# K60.net
KiCad netlist of a schematic drawn in Altium Designer
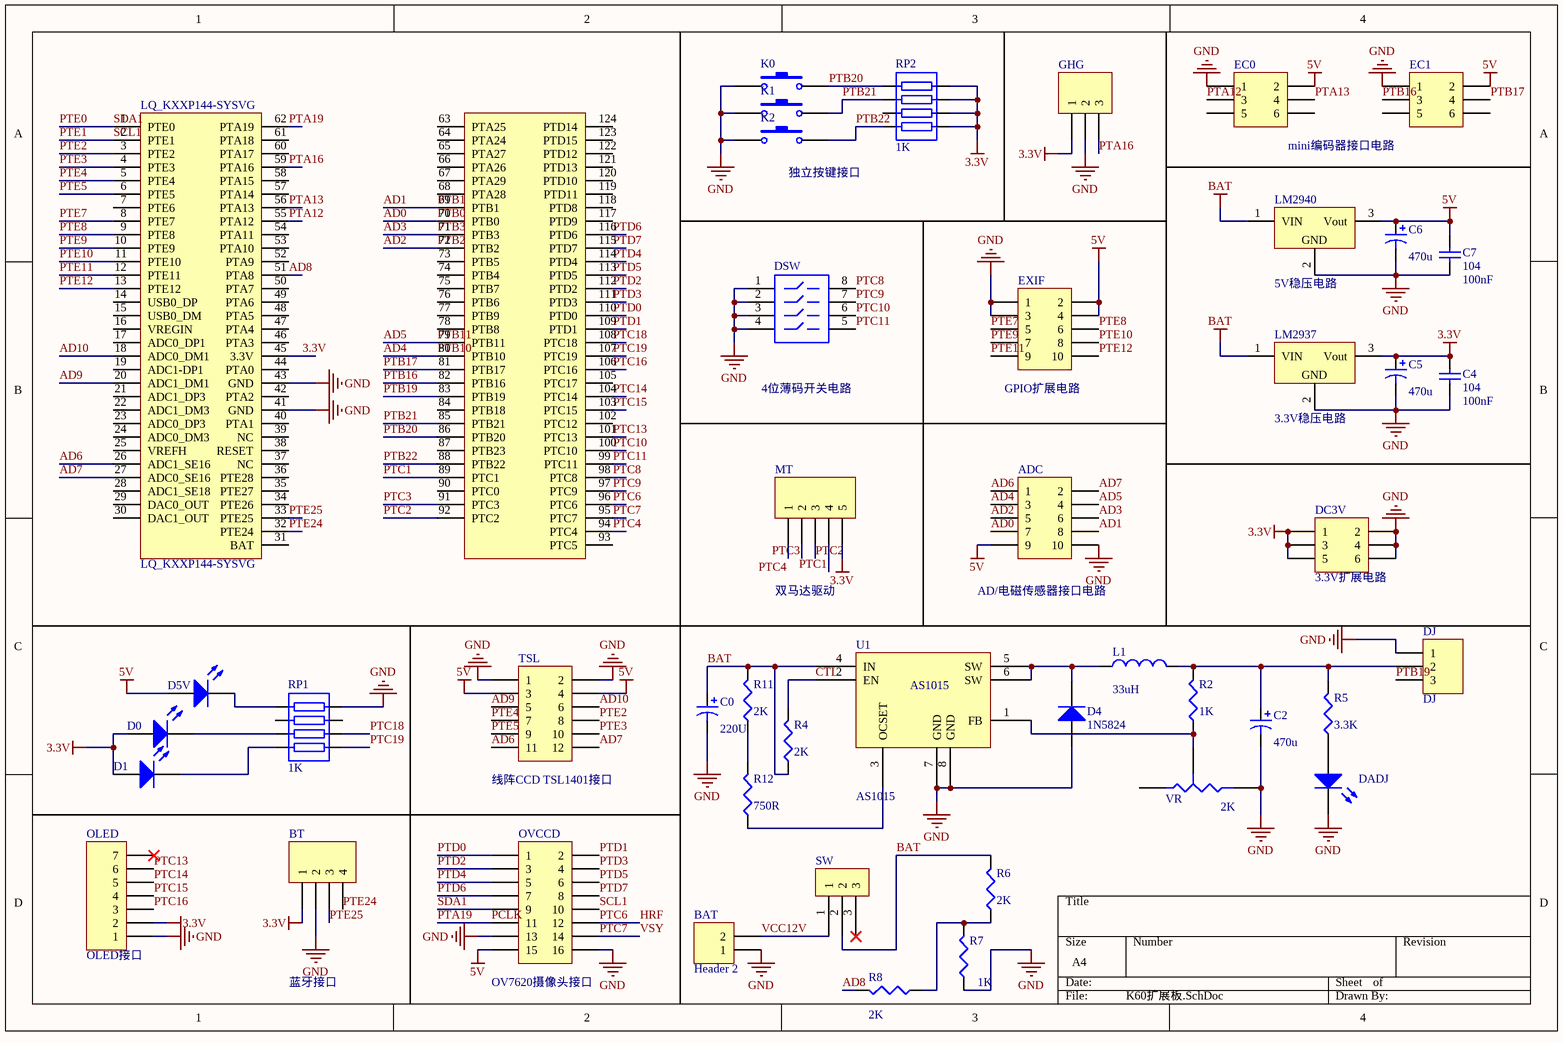
[diagram p0: K60扩展板.SchDoc]

(export (version "E")
  (design (tool "Eeschema 10.0.6"))
  (components
    (comp (ref "ADC")
      (value "AD/电磁传感器接口电路")
      (footprint "HDR2X5")
      (description "Header, 5-Pin, Dual row")
      (fields (field (name "PUBLISHER") "Altium Limited"))
      (libsource (lib "Miscellaneous Connectors") (part "Header 5X2"))
    )
    (comp (ref "BAT")
      (value "Header 2")
      (footprint "power1")
      (description "Header, 2-Pin")
      (fields (field (name "PUBLISHER") "Altium Limited"))
      (libsource (lib "Miscellaneous Connectors") (part "Header 2"))
    )
    (comp (ref "BT")
      (value "蓝牙接口")
      (footprint "HDR1X4")
      (description "Header, 4-Pin")
      (fields (field (name "PUBLISHER") "Altium Limited"))
      (libsource (lib "Miscellaneous Connectors") (part "Header 4"))
    )
    (comp (ref "C0")
      (value "220U")
      (footprint "rb -5")
      (description "Polarized Capacitor (Radial)")
      (fields (field (name "PUBLISHER") "Altium Limited"))
      (libsource (lib "Miscellaneous Devices") (part "Cap Pol1"))
    )
    (comp (ref "C2")
      (value "470u")
      (footprint "3527")
      (description "Polarized Capacitor (Surface Mount)")
      (fields (field (name "PUBLISHER") "Altium Limited"))
      (libsource (lib "Miscellaneous Devices") (part "Cap Pol3"))
    )
    (comp (ref "C4")
      (value "104")
      (footprint "Miscellaneous Devices:0603")
      (description "Capacitor (Semiconductor SIM Model)")
      (fields (field (name "ALTIUM_VALUE") "100nF") (field (name "PUBLISHER") "Altium Limited"))
      (libsource (lib "Miscellaneous Devices") (part "Cap Semi"))
    )
    (comp (ref "C5")
      (value "470u")
      (footprint "3527")
      (description "Polarized Capacitor (Surface Mount)")
      (fields (field (name "PUBLISHER") "Altium Limited"))
      (libsource (lib "Miscellaneous Devices") (part "Cap Pol3"))
    )
    (comp (ref "C6")
      (value "470u")
      (footprint "3527")
      (description "Polarized Capacitor (Surface Mount)")
      (fields (field (name "PUBLISHER") "Altium Limited"))
      (libsource (lib "Miscellaneous Devices") (part "Cap Pol3"))
    )
    (comp (ref "C7")
      (value "104")
      (footprint "Miscellaneous Devices:0603")
      (description "Capacitor (Semiconductor SIM Model)")
      (fields (field (name "ALTIUM_VALUE") "100nF") (field (name "PUBLISHER") "Altium Limited"))
      (libsource (lib "Miscellaneous Devices") (part "Cap Semi"))
    )
    (comp (ref "D0")
      (value "~")
      (footprint "3.2X1.6X1.1")
      (description "Typical BLUE SiC LED")
      (fields (field (name "PUBLISHER") "Altium Limited"))
      (libsource (lib "Miscellaneous Devices") (part "LED3"))
    )
    (comp (ref "D1")
      (value "~")
      (footprint "3.2X1.6X1.1")
      (description "Typical BLUE SiC LED")
      (fields (field (name "PUBLISHER") "Altium Limited"))
      (libsource (lib "Miscellaneous Devices") (part "LED3"))
    )
    (comp (ref "D4")
      (value "1N5824")
      (footprint "1812_DIODE")
      (description "Default Diode")
      (fields (field (name "PUBLISHER") "Altium Limited"))
      (libsource (lib "Miscellaneous Devices") (part "Diode"))
    )
    (comp (ref "D5V")
      (value "~")
      (footprint "3.2X1.6X1.1")
      (description "Typical BLUE SiC LED")
      (fields (field (name "PUBLISHER") "Altium Limited"))
      (libsource (lib "Miscellaneous Devices") (part "LED3"))
    )
    (comp (ref "DADJ")
      (value "~")
      (footprint "3.2X1.6X1.1")
      (description "Typical BLUE SiC LED")
      (fields (field (name "PUBLISHER") "Altium Limited"))
      (libsource (lib "Miscellaneous Devices") (part "LED3"))
    )
    (comp (ref "DC3V")
      (value "3.3V扩展电路")
      (footprint "HDR2X3")
      (description "Header, 3-Pin, Dual row, Right Angle")
      (fields (field (name "PUBLISHER") "Altium Limited"))
      (libsource (lib "Miscellaneous Connectors") (part "Header 3X2H"))
    )
    (comp (ref "DJ")
      (value "DJ")
      (footprint "HDR1X3")
      (description "Header, 3-Pin")
      (fields (field (name "PUBLISHER") "Altium Limited"))
      (libsource (lib "Miscellaneous Connectors") (part "Header 3"))
    )
    (comp (ref "DSW")
      (value "4位薄码开关电路")
      (footprint "DIP-8")
      (description "DIP Switch")
      (fields (field (name "PUBLISHER") "Altium Limited"))
      (libsource (lib "Miscellaneous Devices") (part "SW-DIP4"))
    )
    (comp (ref "EC0")
      (value "~")
      (footprint "HDR2X3")
      (description "Header, 3-Pin, Dual row")
      (fields (field (name "PUBLISHER") "Altium Limited"))
      (libsource (lib "Miscellaneous Connectors") (part "Header 3X2"))
    )
    (comp (ref "EC1")
      (value "mini编码器接口电路")
      (footprint "HDR2X3")
      (description "Header, 3-Pin, Dual row")
      (fields (field (name "PUBLISHER") "Altium Limited"))
      (libsource (lib "Miscellaneous Connectors") (part "Header 3X2"))
    )
    (comp (ref "EXIF")
      (value "GPIO扩展电路")
      (footprint "HDR2X5")
      (description "Header, 5-Pin, Dual row")
      (fields (field (name "PUBLISHER") "Altium Limited"))
      (libsource (lib "Miscellaneous Connectors") (part "Header 5X2"))
    )
    (comp (ref "GHG")
      (value "~")
      (footprint "HDR1X3")
      (description "Header, 3-Pin")
      (fields (field (name "PUBLISHER") "Altium Limited"))
      (libsource (lib "") (part "Header 3_1"))
    )
    (comp (ref "K0")
      (value "~")
      (footprint "2512R")
      (description "Switch")
      (fields (field (name "PUBLISHER") "Altium Limited"))
      (libsource (lib "Miscellaneous Devices") (part "SW-PB"))
    )
    (comp (ref "K1")
      (value "~")
      (footprint "2512R")
      (description "Switch")
      (fields (field (name "PUBLISHER") "Altium Limited"))
      (libsource (lib "Miscellaneous Devices") (part "SW-PB"))
    )
    (comp (ref "K2")
      (value "~")
      (footprint "2512R")
      (description "Switch")
      (fields (field (name "PUBLISHER") "Altium Limited"))
      (libsource (lib "Miscellaneous Devices") (part "SW-PB"))
    )
    (comp (ref "L1")
      (value "33uH")
      (footprint "CL1010")
      (description "Inductor")
      (fields (field (name "PUBLISHER") "Altium Limited"))
      (libsource (lib "Miscellaneous Devices") (part "Inductor"))
    )
    (comp (ref "LM2937")
      (value "3.3V稳压电路")
      (footprint "TO263-3")
      (description "固定5V输出直流稳压芯片")
      (libsource (lib "常用贴片器件库") (part "LM2940"))
    )
    (comp (ref "LM2940")
      (value "5V稳压电路")
      (footprint "TO263-3")
      (description "固定5V输出直流稳压芯片")
      (libsource (lib "常用贴片器件库") (part "LM2940"))
    )
    (comp (ref "LQ_KXXP144-SYSVG")
      (value "LQ_KXXP144-SYSVG")
      (footprint "LQ_KXXP144-SYSVG")
      (libsource (lib "LQ_KXXP144-SYSVGSCH") (part "LQ_KXXP144-SYSVG"))
    )
    (comp (ref "MT")
      (value "双马达驱动")
      (footprint "HDR1X5")
      (description "Header, 5-Pin")
      (fields (field (name "PUBLISHER") "Altium Limited"))
      (libsource (lib "Miscellaneous Connectors") (part "Header 5"))
    )
    (comp (ref "OLED")
      (value "OLED接口")
      (footprint "HDR1X7")
      (description "Header, 7-Pin")
      (fields (field (name "PUBLISHER") "Altium Limited"))
      (libsource (lib "Miscellaneous Connectors") (part "Header 7"))
    )
    (comp (ref "OVCCD")
      (value "OV7620摄像头接口")
      (footprint "HDR2X8")
      (description "Header, 8-Pin, Dual row")
      (fields (field (name "PUBLISHER") "Altium Limited"))
      (libsource (lib "Miscellaneous Connectors") (part "Header 8X2"))
    )
    (comp (ref "R2")
      (value "1K")
      (footprint "J1-0603")
      (description "Resistor")
      (fields (field (name "PUBLISHER") "Altium Limited"))
      (libsource (lib "Miscellaneous Devices") (part "Res3"))
    )
    (comp (ref "R4")
      (value "2K")
      (footprint "J1-0603")
      (description "Resistor")
      (fields (field (name "PUBLISHER") "Altium Limited"))
      (libsource (lib "Miscellaneous Devices") (part "Res3"))
    )
    (comp (ref "R5")
      (value "3.3K")
      (footprint "J1-0603")
      (description "Resistor")
      (fields (field (name "PUBLISHER") "Altium Limited"))
      (libsource (lib "Miscellaneous Devices") (part "Res3"))
    )
    (comp (ref "R6")
      (value "2K")
      (footprint "J1-0603")
      (description "Resistor")
      (fields (field (name "PUBLISHER") "Altium Limited"))
      (libsource (lib "Miscellaneous Devices") (part "Res3"))
    )
    (comp (ref "R7")
      (value "1K")
      (footprint "J1-0603")
      (description "Resistor")
      (fields (field (name "PUBLISHER") "Altium Limited"))
      (libsource (lib "Miscellaneous Devices") (part "Res3"))
    )
    (comp (ref "R8")
      (value "2K")
      (footprint "J1-0603")
      (description "Resistor")
      (fields (field (name "PUBLISHER") "Altium Limited"))
      (libsource (lib "Miscellaneous Devices") (part "Res3"))
    )
    (comp (ref "R11")
      (value "2K")
      (footprint "J1-0603")
      (description "Resistor")
      (fields (field (name "PUBLISHER") "Altium Limited"))
      (libsource (lib "Miscellaneous Devices") (part "Res3"))
    )
    (comp (ref "R12")
      (value "750R")
      (footprint "J1-0603")
      (description "Resistor")
      (fields (field (name "PUBLISHER") "Altium Limited"))
      (libsource (lib "Miscellaneous Devices") (part "Res3"))
    )
    (comp (ref "RP1") (value "1K") (footprint "RESPACK4_SMD") (libsource (lib "常用器件库_SCH") (part "RESPACK4")))
    (comp (ref "RP2") (value "1K") (footprint "RESPACK4_SMD") (libsource (lib "常用器件库_SCH") (part "RESPACK4")))
    (comp (ref "SW") (value "~") (footprint "钮子开关 - duplicate") (libsource (lib "钮子开关") (part "钮子开关")))
    (comp (ref "TSL")
      (value "线阵CCD TSL1401接口")
      (footprint "HDR2X6")
      (description "Header, 6-Pin, Dual row")
      (fields (field (name "PUBLISHER") "Altium Limited"))
      (libsource (lib "Miscellaneous Connectors") (part "Header 6X2"))
    )
    (comp (ref "U1") (value "AS1015") (footprint "SOP8L") (libsource (lib "my") (part "AS1015")))
    (comp (ref "VR")
      (value "2K")
      (footprint "3362")
      (description "Tapped Resistor")
      (fields (field (name "PUBLISHER") "Altium Limited"))
      (libsource (lib "Miscellaneous Devices") (part "Res Tap"))
    )
  )
  (nets
    (net (code "1") (name "/AD0") (class "Default")
      (node (ref "ADC") (pin "7") (pinfunction "7_7") (pintype "passive"))
      (node (ref "LQ_KXXP144-SYSVG") (pin "70") (pinfunction "PTB0_70") (pintype "passive"))
    )
    (net (code "2") (name "/AD1") (class "Default")
      (node (ref "ADC") (pin "8") (pinfunction "8_8") (pintype "passive"))
      (node (ref "LQ_KXXP144-SYSVG") (pin "69") (pinfunction "PTB1_69") (pintype "passive"))
    )
    (net (code "3") (name "/AD2") (class "Default")
      (node (ref "ADC") (pin "5") (pinfunction "5_5") (pintype "passive"))
      (node (ref "LQ_KXXP144-SYSVG") (pin "72") (pinfunction "PTB2_72") (pintype "passive"))
    )
    (net (code "4") (name "/AD3") (class "Default")
      (node (ref "ADC") (pin "6") (pinfunction "6_6") (pintype "passive"))
      (node (ref "LQ_KXXP144-SYSVG") (pin "71") (pinfunction "PTB3_71") (pintype "passive"))
    )
    (net (code "5") (name "/AD4") (class "Default")
      (node (ref "ADC") (pin "3") (pinfunction "3_3") (pintype "passive"))
      (node (ref "LQ_KXXP144-SYSVG") (pin "80") (pinfunction "PTB10_80") (pintype "passive"))
    )
    (net (code "6") (name "/AD5") (class "Default")
      (node (ref "ADC") (pin "4") (pinfunction "4_4") (pintype "passive"))
      (node (ref "LQ_KXXP144-SYSVG") (pin "79") (pinfunction "PTB11_79") (pintype "passive"))
    )
    (net (code "7") (name "/AD6") (class "Default")
      (node (ref "ADC") (pin "1") (pinfunction "1_1") (pintype "passive"))
      (node (ref "LQ_KXXP144-SYSVG") (pin "26") (pinfunction "ADC1_SE16_26") (pintype "passive"))
      (node (ref "TSL") (pin "11") (pinfunction "11_11") (pintype "passive"))
    )
    (net (code "8") (name "/AD7") (class "Default")
      (node (ref "ADC") (pin "2") (pinfunction "2_2") (pintype "passive"))
      (node (ref "LQ_KXXP144-SYSVG") (pin "27") (pinfunction "ADC0_SE16_27") (pintype "passive"))
      (node (ref "TSL") (pin "12") (pinfunction "12_12") (pintype "passive"))
    )
    (net (code "9") (name "/AD8") (class "Default")
      (node (ref "LQ_KXXP144-SYSVG") (pin "51") (pinfunction "PTA8_51") (pintype "passive"))
      (node (ref "R8") (pin "2") (pinfunction "2_2") (pintype "passive"))
    )
    (net (code "10") (name "/AD9") (class "Default")
      (node (ref "LQ_KXXP144-SYSVG") (pin "20") (pinfunction "ADC1_DM1_20") (pintype "passive"))
      (node (ref "TSL") (pin "5") (pinfunction "5_5") (pintype "passive"))
    )
    (net (code "11") (name "/AD10") (class "Default")
      (node (ref "LQ_KXXP144-SYSVG") (pin "18") (pinfunction "ADC0_DM1_18") (pintype "passive"))
      (node (ref "TSL") (pin "6") (pinfunction "6_6") (pintype "passive"))
    )
    (net (code "12") (name "/CTL") (class "Default")
      (node (ref "R4") (pin "2") (pinfunction "2_2") (pintype "passive"))
      (node (ref "U1") (pin "2") (pinfunction "EN_2") (pintype "passive"))
    )
    (net (code "13") (name "/HRF") (class "Default")
      (node (ref "LQ_KXXP144-SYSVG") (pin "96") (pinfunction "PTC6_96") (pintype "passive"))
      (node (ref "OVCCD") (pin "12") (pinfunction "12_12") (pintype "passive"))
    )
    (net (code "14") (name "/PCLK") (class "Default")
      (node (ref "LQ_KXXP144-SYSVG") (pin "62") (pinfunction "PTA19_62") (pintype "passive"))
      (node (ref "OVCCD") (pin "11") (pinfunction "11_11") (pintype "passive"))
    )
    (net (code "15") (name "/PTA12") (class "Default")
      (node (ref "EC0") (pin "3") (pinfunction "3_3") (pintype "passive"))
      (node (ref "LQ_KXXP144-SYSVG") (pin "55") (pinfunction "PTA12_55") (pintype "passive"))
    )
    (net (code "16") (name "/PTA13") (class "Default")
      (node (ref "EC0") (pin "4") (pinfunction "4_4") (pintype "passive"))
      (node (ref "LQ_KXXP144-SYSVG") (pin "56") (pinfunction "PTA13_56") (pintype "passive"))
    )
    (net (code "17") (name "/PTA16") (class "Default")
      (node (ref "GHG") (pin "3") (pinfunction "3_3") (pintype "passive"))
      (node (ref "LQ_KXXP144-SYSVG") (pin "59") (pinfunction "PTA16_59") (pintype "passive"))
    )
    (net (code "18") (name "/PTB16") (class "Default")
      (node (ref "EC1") (pin "3") (pinfunction "3_3") (pintype "passive"))
      (node (ref "LQ_KXXP144-SYSVG") (pin "82") (pinfunction "PTB16_82") (pintype "passive"))
    )
    (net (code "19") (name "/PTB17") (class "Default")
      (node (ref "EC1") (pin "4") (pinfunction "4_4") (pintype "passive"))
      (node (ref "LQ_KXXP144-SYSVG") (pin "81") (pinfunction "PTB17_81") (pintype "passive"))
    )
    (net (code "20") (name "/PTB19") (class "Default")
      (node (ref "DJ") (pin "3") (pinfunction "3_3") (pintype "passive"))
      (node (ref "LQ_KXXP144-SYSVG") (pin "83") (pinfunction "PTB19_83") (pintype "passive"))
    )
    (net (code "21") (name "/PTB20") (class "Default")
      (node (ref "K0") (pin "2") (pinfunction "2_2") (pintype "passive"))
      (node (ref "LQ_KXXP144-SYSVG") (pin "86") (pinfunction "PTB20_86") (pintype "passive"))
      (node (ref "RP2") (pin "1") (pintype "passive"))
    )
    (net (code "22") (name "/PTB21") (class "Default")
      (node (ref "K1") (pin "2") (pinfunction "2_2") (pintype "passive"))
      (node (ref "LQ_KXXP144-SYSVG") (pin "85") (pinfunction "PTB21_85") (pintype "passive"))
      (node (ref "RP2") (pin "3") (pintype "passive"))
    )
    (net (code "23") (name "/PTB22") (class "Default")
      (node (ref "K2") (pin "2") (pinfunction "2_2") (pintype "passive"))
      (node (ref "LQ_KXXP144-SYSVG") (pin "88") (pinfunction "PTB22_88") (pintype "passive"))
      (node (ref "RP2") (pin "7") (pintype "passive"))
    )
    (net (code "24") (name "/PTC1") (class "Default")
      (node (ref "LQ_KXXP144-SYSVG") (pin "89") (pinfunction "PTC1_89") (pintype "passive"))
      (node (ref "MT") (pin "4") (pinfunction "4_4") (pintype "passive"))
    )
    (net (code "25") (name "/PTC2") (class "Default")
      (node (ref "LQ_KXXP144-SYSVG") (pin "92") (pinfunction "PTC2_92") (pintype "passive"))
      (node (ref "MT") (pin "3") (pinfunction "3_3") (pintype "passive"))
    )
    (net (code "26") (name "/PTC3") (class "Default")
      (node (ref "LQ_KXXP144-SYSVG") (pin "91") (pinfunction "PTC3_91") (pintype "passive"))
      (node (ref "MT") (pin "2") (pinfunction "2_2") (pintype "passive"))
    )
    (net (code "27") (name "/PTC4") (class "Default")
      (node (ref "LQ_KXXP144-SYSVG") (pin "94") (pinfunction "PTC4_94") (pintype "passive"))
      (node (ref "MT") (pin "1") (pinfunction "1_1") (pintype "passive"))
    )
    (net (code "28") (name "/PTC7") (class "Default")
      (node (ref "LQ_KXXP144-SYSVG") (pin "95") (pinfunction "PTC7_95") (pintype "passive"))
      (node (ref "OVCCD") (pin "14") (pinfunction "14_14") (pintype "passive"))
    )
    (net (code "29") (name "/PTC8") (class "Default")
      (node (ref "DSW") (pin "8") (pinfunction "8_8") (pintype "passive"))
      (node (ref "LQ_KXXP144-SYSVG") (pin "98") (pinfunction "PTC8_98") (pintype "passive"))
    )
    (net (code "30") (name "/PTC9") (class "Default")
      (node (ref "DSW") (pin "7") (pinfunction "7_7") (pintype "passive"))
      (node (ref "LQ_KXXP144-SYSVG") (pin "97") (pinfunction "PTC9_97") (pintype "passive"))
    )
    (net (code "31") (name "/PTC10") (class "Default")
      (node (ref "DSW") (pin "6") (pinfunction "6_6") (pintype "passive"))
      (node (ref "LQ_KXXP144-SYSVG") (pin "100") (pinfunction "PTC10_100") (pintype "passive"))
    )
    (net (code "32") (name "/PTC11") (class "Default")
      (node (ref "DSW") (pin "5") (pinfunction "5_5") (pintype "passive"))
      (node (ref "LQ_KXXP144-SYSVG") (pin "99") (pinfunction "PTC11_99") (pintype "passive"))
    )
    (net (code "33") (name "/PTC13") (class "Default")
      (node (ref "LQ_KXXP144-SYSVG") (pin "101") (pinfunction "PTC13_101") (pintype "passive"))
      (node (ref "OLED") (pin "6") (pinfunction "6_6") (pintype "passive"))
    )
    (net (code "34") (name "/PTC14") (class "Default")
      (node (ref "LQ_KXXP144-SYSVG") (pin "104") (pinfunction "PTC14_104") (pintype "passive"))
      (node (ref "OLED") (pin "5") (pinfunction "5_5") (pintype "passive"))
    )
    (net (code "35") (name "/PTC15") (class "Default")
      (node (ref "LQ_KXXP144-SYSVG") (pin "103") (pinfunction "PTC15_103") (pintype "passive"))
      (node (ref "OLED") (pin "4") (pinfunction "4_4") (pintype "passive"))
    )
    (net (code "36") (name "/PTC16") (class "Default")
      (node (ref "LQ_KXXP144-SYSVG") (pin "106") (pinfunction "PTC16_106") (pintype "passive"))
      (node (ref "OLED") (pin "3") (pinfunction "3_3") (pintype "passive"))
    )
    (net (code "37") (name "/PTC18") (class "Default")
      (node (ref "LQ_KXXP144-SYSVG") (pin "108") (pinfunction "PTC18_108") (pintype "passive"))
      (node (ref "RP1") (pin "6") (pintype "passive"))
    )
    (net (code "38") (name "/PTC19") (class "Default")
      (node (ref "LQ_KXXP144-SYSVG") (pin "107") (pinfunction "PTC19_107") (pintype "passive"))
      (node (ref "RP1") (pin "8") (pintype "passive"))
    )
    (net (code "39") (name "/PTD0") (class "Default")
      (node (ref "LQ_KXXP144-SYSVG") (pin "110") (pinfunction "PTD0_110") (pintype "passive"))
      (node (ref "OVCCD") (pin "1") (pinfunction "1_1") (pintype "passive"))
    )
    (net (code "40") (name "/PTD1") (class "Default")
      (node (ref "LQ_KXXP144-SYSVG") (pin "109") (pinfunction "PTD1_109") (pintype "passive"))
      (node (ref "OVCCD") (pin "2") (pinfunction "2_2") (pintype "passive"))
    )
    (net (code "41") (name "/PTD2") (class "Default")
      (node (ref "LQ_KXXP144-SYSVG") (pin "112") (pinfunction "PTD2_112") (pintype "passive"))
      (node (ref "OVCCD") (pin "3") (pinfunction "3_3") (pintype "passive"))
    )
    (net (code "42") (name "/PTD3") (class "Default")
      (node (ref "LQ_KXXP144-SYSVG") (pin "111") (pinfunction "PTD3_111") (pintype "passive"))
      (node (ref "OVCCD") (pin "4") (pinfunction "4_4") (pintype "passive"))
    )
    (net (code "43") (name "/PTD4") (class "Default")
      (node (ref "LQ_KXXP144-SYSVG") (pin "114") (pinfunction "PTD4_114") (pintype "passive"))
      (node (ref "OVCCD") (pin "5") (pinfunction "5_5") (pintype "passive"))
    )
    (net (code "44") (name "/PTD5") (class "Default")
      (node (ref "LQ_KXXP144-SYSVG") (pin "113") (pinfunction "PTD5_113") (pintype "passive"))
      (node (ref "OVCCD") (pin "6") (pinfunction "6_6") (pintype "passive"))
    )
    (net (code "45") (name "/PTD6") (class "Default")
      (node (ref "LQ_KXXP144-SYSVG") (pin "116") (pinfunction "PTD6_116") (pintype "passive"))
      (node (ref "OVCCD") (pin "7") (pinfunction "7_7") (pintype "passive"))
    )
    (net (code "46") (name "/PTD7") (class "Default")
      (node (ref "LQ_KXXP144-SYSVG") (pin "115") (pinfunction "PTD7_115") (pintype "passive"))
      (node (ref "OVCCD") (pin "8") (pinfunction "8_8") (pintype "passive"))
    )
    (net (code "47") (name "/PTE0") (class "Default")
      (node (ref "LQ_KXXP144-SYSVG") (pin "1") (pinfunction "PTE0_1") (pintype "passive"))
      (node (ref "OVCCD") (pin "9") (pinfunction "9_9") (pintype "passive"))
    )
    (net (code "48") (name "/PTE1") (class "Default")
      (node (ref "LQ_KXXP144-SYSVG") (pin "2") (pinfunction "PTE1_2") (pintype "passive"))
      (node (ref "OVCCD") (pin "10") (pinfunction "10_10") (pintype "passive"))
    )
    (net (code "49") (name "/PTE2") (class "Default")
      (node (ref "LQ_KXXP144-SYSVG") (pin "3") (pinfunction "PTE2_3") (pintype "passive"))
      (node (ref "TSL") (pin "8") (pinfunction "8_8") (pintype "passive"))
    )
    (net (code "50") (name "/PTE3") (class "Default")
      (node (ref "LQ_KXXP144-SYSVG") (pin "4") (pinfunction "PTE3_4") (pintype "passive"))
      (node (ref "TSL") (pin "10") (pinfunction "10_10") (pintype "passive"))
    )
    (net (code "51") (name "/PTE4") (class "Default")
      (node (ref "LQ_KXXP144-SYSVG") (pin "5") (pinfunction "PTE4_5") (pintype "passive"))
      (node (ref "TSL") (pin "7") (pinfunction "7_7") (pintype "passive"))
    )
    (net (code "52") (name "/PTE5") (class "Default")
      (node (ref "LQ_KXXP144-SYSVG") (pin "6") (pinfunction "PTE5_6") (pintype "passive"))
      (node (ref "TSL") (pin "9") (pinfunction "9_9") (pintype "passive"))
    )
    (net (code "53") (name "/PTE7") (class "Default")
      (node (ref "EXIF") (pin "5") (pinfunction "5_5") (pintype "passive"))
      (node (ref "LQ_KXXP144-SYSVG") (pin "8") (pinfunction "PTE7_8") (pintype "passive"))
    )
    (net (code "54") (name "/PTE8") (class "Default")
      (node (ref "EXIF") (pin "6") (pinfunction "6_6") (pintype "passive"))
      (node (ref "LQ_KXXP144-SYSVG") (pin "9") (pinfunction "PTE8_9") (pintype "passive"))
    )
    (net (code "55") (name "/PTE9") (class "Default")
      (node (ref "EXIF") (pin "7") (pinfunction "7_7") (pintype "passive"))
      (node (ref "LQ_KXXP144-SYSVG") (pin "10") (pinfunction "PTE9_10") (pintype "passive"))
    )
    (net (code "56") (name "/PTE10") (class "Default")
      (node (ref "EXIF") (pin "8") (pinfunction "8_8") (pintype "passive"))
      (node (ref "LQ_KXXP144-SYSVG") (pin "11") (pinfunction "PTE10_11") (pintype "passive"))
    )
    (net (code "57") (name "/PTE11") (class "Default")
      (node (ref "EXIF") (pin "9") (pinfunction "9_9") (pintype "passive"))
      (node (ref "LQ_KXXP144-SYSVG") (pin "12") (pinfunction "PTE11_12") (pintype "passive"))
    )
    (net (code "58") (name "/PTE12") (class "Default")
      (node (ref "EXIF") (pin "10") (pinfunction "10_10") (pintype "passive"))
      (node (ref "LQ_KXXP144-SYSVG") (pin "13") (pinfunction "PTE12_13") (pintype "passive"))
    )
    (net (code "59") (name "/PTE24") (class "Default")
      (node (ref "BT") (pin "4") (pinfunction "4_4") (pintype "passive"))
      (node (ref "LQ_KXXP144-SYSVG") (pin "32") (pinfunction "PTE24_32") (pintype "passive"))
    )
    (net (code "60") (name "/PTE25") (class "Default")
      (node (ref "BT") (pin "3") (pinfunction "3_3") (pintype "passive"))
      (node (ref "LQ_KXXP144-SYSVG") (pin "33") (pinfunction "PTE25_33") (pintype "passive"))
    )
    (net (code "61") (name "/VCC12V") (class "Default")
      (node (ref "BAT") (pin "2") (pinfunction "2_2") (pintype "passive"))
      (node (ref "SW") (pin "1") (pinfunction "1_1") (pintype "passive"))
    )
    (net (code "62") (name "3.3V") (class "Default")
      (node (ref "BT") (pin "1") (pinfunction "1_1") (pintype "passive"))
      (node (ref "C4") (pin "2") (pinfunction "2_2") (pintype "passive"))
      (node (ref "C5") (pin "1") (pinfunction "1_1") (pintype "passive"))
      (node (ref "D0") (pin "1") (pinfunction "A_1") (pintype "passive"))
      (node (ref "D1") (pin "1") (pinfunction "A_1") (pintype "passive"))
      (node (ref "DC3V") (pin "1") (pinfunction "1_1") (pintype "passive"))
      (node (ref "DC3V") (pin "3") (pinfunction "3_3") (pintype "passive"))
      (node (ref "DC3V") (pin "5") (pinfunction "5_5") (pintype "passive"))
      (node (ref "GHG") (pin "1") (pinfunction "1_1") (pintype "passive"))
      (node (ref "LM2937") (pin "3") (pinfunction "Vout_3") (pintype "passive"))
      (node (ref "LQ_KXXP144-SYSVG") (pin "45") (pinfunction "3.3V_45") (pintype "passive"))
      (node (ref "MT") (pin "5") (pinfunction "5_5") (pintype "passive"))
      (node (ref "OLED") (pin "2") (pinfunction "2_2") (pintype "passive"))
      (node (ref "RP2") (pin "2") (pintype "passive"))
      (node (ref "RP2") (pin "4") (pintype "passive"))
      (node (ref "RP2") (pin "6") (pintype "passive"))
      (node (ref "RP2") (pin "8") (pintype "passive"))
    )
    (net (code "63") (name "5V") (class "Default")
      (node (ref "ADC") (pin "9") (pinfunction "9_9") (pintype "passive"))
      (node (ref "C6") (pin "1") (pinfunction "1_1") (pintype "passive"))
      (node (ref "C7") (pin "2") (pinfunction "2_2") (pintype "passive"))
      (node (ref "D5V") (pin "1") (pinfunction "A_1") (pintype "passive"))
      (node (ref "EC0") (pin "2") (pinfunction "2_2") (pintype "passive"))
      (node (ref "EC1") (pin "2") (pinfunction "2_2") (pintype "passive"))
      (node (ref "EXIF") (pin "2") (pinfunction "2_2") (pintype "passive"))
      (node (ref "EXIF") (pin "4") (pinfunction "4_4") (pintype "passive"))
      (node (ref "LM2940") (pin "3") (pinfunction "Vout_3") (pintype "passive"))
      (node (ref "OVCCD") (pin "15") (pinfunction "15_15") (pintype "passive"))
      (node (ref "TSL") (pin "3") (pinfunction "3_3") (pintype "passive"))
      (node (ref "TSL") (pin "4") (pinfunction "4_4") (pintype "passive"))
    )
    (net (code "64") (name "BAT") (class "Default")
      (node (ref "C0") (pin "1") (pinfunction "1_1") (pintype "passive"))
      (node (ref "LM2937") (pin "1") (pinfunction "VIN_1") (pintype "passive"))
      (node (ref "LM2940") (pin "1") (pinfunction "VIN_1") (pintype "passive"))
      (node (ref "R11") (pin "2") (pinfunction "2_2") (pintype "passive"))
      (node (ref "R4") (pin "1") (pinfunction "1_1") (pintype "passive"))
      (node (ref "R6") (pin "2") (pinfunction "2_2") (pintype "passive"))
      (node (ref "SW") (pin "2") (pinfunction "2_2") (pintype "passive"))
      (node (ref "U1") (pin "4") (pinfunction "IN_4") (pintype "passive"))
    )
    (net (code "65") (name "GND") (class "Default")
      (node (ref "ADC") (pin "10") (pinfunction "10_10") (pintype "passive"))
      (node (ref "BAT") (pin "1") (pinfunction "1_1") (pintype "passive"))
      (node (ref "BT") (pin "2") (pinfunction "2_2") (pintype "passive"))
      (node (ref "C0") (pin "2") (pinfunction "2_2") (pintype "passive"))
      (node (ref "C2") (pin "2") (pinfunction "2_2") (pintype "passive"))
      (node (ref "C4") (pin "1") (pinfunction "1_1") (pintype "passive"))
      (node (ref "C5") (pin "2") (pinfunction "2_2") (pintype "passive"))
      (node (ref "C6") (pin "2") (pinfunction "2_2") (pintype "passive"))
      (node (ref "C7") (pin "1") (pinfunction "1_1") (pintype "passive"))
      (node (ref "D4") (pin "1") (pinfunction "A_1") (pintype "passive"))
      (node (ref "DADJ") (pin "2") (pinfunction "K_2") (pintype "passive"))
      (node (ref "DC3V") (pin "2") (pinfunction "2_2") (pintype "passive"))
      (node (ref "DC3V") (pin "4") (pinfunction "4_4") (pintype "passive"))
      (node (ref "DC3V") (pin "6") (pinfunction "6_6") (pintype "passive"))
      (node (ref "DJ") (pin "1") (pinfunction "1_1") (pintype "passive"))
      (node (ref "DSW") (pin "1") (pinfunction "1_1") (pintype "passive"))
      (node (ref "DSW") (pin "2") (pinfunction "2_2") (pintype "passive"))
      (node (ref "DSW") (pin "3") (pinfunction "3_3") (pintype "passive"))
      (node (ref "DSW") (pin "4") (pinfunction "4_4") (pintype "passive"))
      (node (ref "EC0") (pin "1") (pinfunction "1_1") (pintype "passive"))
      (node (ref "EC1") (pin "1") (pinfunction "1_1") (pintype "passive"))
      (node (ref "EXIF") (pin "1") (pinfunction "1_1") (pintype "passive"))
      (node (ref "EXIF") (pin "3") (pinfunction "3_3") (pintype "passive"))
      (node (ref "GHG") (pin "2") (pinfunction "2_2") (pintype "passive"))
      (node (ref "K0") (pin "1") (pinfunction "1_1") (pintype "passive"))
      (node (ref "K1") (pin "1") (pinfunction "1_1") (pintype "passive"))
      (node (ref "K2") (pin "1") (pinfunction "1_1") (pintype "passive"))
      (node (ref "LM2937") (pin "2") (pinfunction "GND_2") (pintype "passive"))
      (node (ref "LM2940") (pin "2") (pinfunction "GND_2") (pintype "passive"))
      (node (ref "LQ_KXXP144-SYSVG") (pin "41") (pinfunction "GND_41") (pintype "passive"))
      (node (ref "LQ_KXXP144-SYSVG") (pin "43") (pinfunction "GND_43") (pintype "passive"))
      (node (ref "OLED") (pin "1") (pinfunction "1_1") (pintype "passive"))
      (node (ref "OVCCD") (pin "13") (pinfunction "13_13") (pintype "passive"))
      (node (ref "OVCCD") (pin "16") (pinfunction "16_16") (pintype "passive"))
      (node (ref "R7") (pin "1") (pinfunction "1_1") (pintype "passive"))
      (node (ref "RP1") (pin "2") (pintype "passive"))
      (node (ref "TSL") (pin "1") (pinfunction "1_1") (pintype "passive"))
      (node (ref "TSL") (pin "2") (pinfunction "2_2") (pintype "passive"))
      (node (ref "U1") (pin "7") (pinfunction "GND_7") (pintype "passive"))
      (node (ref "U1") (pin "8") (pinfunction "GND_8") (pintype "passive"))
      (node (ref "VR") (pin "2") (pinfunction "B_2") (pintype "passive"))
    )
    (net (code "66") (name "Net-(C2-Pad1)") (class "Default")
      (node (ref "C2") (pin "1") (pinfunction "1_1") (pintype "passive"))
      (node (ref "DJ") (pin "2") (pinfunction "2_2") (pintype "passive"))
      (node (ref "L1") (pin "2") (pinfunction "2_2") (pintype "passive"))
      (node (ref "R2") (pin "2") (pinfunction "2_2") (pintype "passive"))
      (node (ref "R5") (pin "2") (pinfunction "2_2") (pintype "passive"))
    )
    (net (code "67") (name "Net-(D0-K)") (class "Default")
      (node (ref "D0") (pin "2") (pinfunction "K_2") (pintype "passive"))
      (node (ref "RP1") (pin "5") (pintype "passive"))
    )
    (net (code "68") (name "Net-(D1-K)") (class "Default")
      (node (ref "D1") (pin "2") (pinfunction "K_2") (pintype "passive"))
      (node (ref "RP1") (pin "7") (pintype "passive"))
    )
    (net (code "69") (name "Net-(D4-K)") (class "Default")
      (node (ref "D4") (pin "2") (pinfunction "K_2") (pintype "passive"))
      (node (ref "L1") (pin "1") (pinfunction "1_1") (pintype "passive"))
      (node (ref "U1") (pin "5") (pinfunction "SW_5") (pintype "passive"))
      (node (ref "U1") (pin "6") (pinfunction "SW_6") (pintype "passive"))
    )
    (net (code "70") (name "Net-(D5V-K)") (class "Default")
      (node (ref "D5V") (pin "2") (pinfunction "K_2") (pintype "passive"))
      (node (ref "RP1") (pin "1") (pintype "passive"))
    )
    (net (code "71") (name "Net-(DADJ-A)") (class "Default")
      (node (ref "DADJ") (pin "1") (pinfunction "A_1") (pintype "passive"))
      (node (ref "R5") (pin "1") (pinfunction "1_1") (pintype "passive"))
    )
    (net (code "72") (name "Net-(R6-Pad1)") (class "Default")
      (node (ref "R6") (pin "1") (pinfunction "1_1") (pintype "passive"))
      (node (ref "R7") (pin "2") (pinfunction "2_2") (pintype "passive"))
      (node (ref "R8") (pin "1") (pinfunction "1_1") (pintype "passive"))
    )
    (net (code "73") (name "Net-(R11-Pad1)") (class "Default")
      (node (ref "R11") (pin "1") (pinfunction "1_1") (pintype "passive"))
      (node (ref "R12") (pin "2") (pinfunction "2_2") (pintype "passive"))
    )
    (net (code "74") (name "Net-(U1-FB)") (class "Default")
      (node (ref "R2") (pin "1") (pinfunction "1_1") (pintype "passive"))
      (node (ref "U1") (pin "1") (pinfunction "FB_1") (pintype "passive"))
      (node (ref "VR") (pin "3") (pinfunction "TAP_3") (pintype "passive"))
    )
    (net (code "75") (name "Net-(U1-OCSET)") (class "Default")
      (node (ref "R12") (pin "1") (pinfunction "1_1") (pintype "passive"))
      (node (ref "U1") (pin "3") (pinfunction "OCSET_3") (pintype "passive"))
    )
    (net (code "76") (name "unconnected-(EC0-Pad5)") (class "Default")
      (node (ref "EC0") (pin "5") (pinfunction "5_5") (pintype "passive"))
    )
    (net (code "77") (name "unconnected-(EC0-Pad6)") (class "Default")
      (node (ref "EC0") (pin "6") (pinfunction "6_6") (pintype "passive"))
    )
    (net (code "78") (name "unconnected-(EC1-Pad5)") (class "Default")
      (node (ref "EC1") (pin "5") (pinfunction "5_5") (pintype "passive"))
    )
    (net (code "79") (name "unconnected-(EC1-Pad6)") (class "Default")
      (node (ref "EC1") (pin "6") (pinfunction "6_6") (pintype "passive"))
    )
    (net (code "80") (name "unconnected-(LQ_KXXP144-SYSVG-ADC0_DM3-Pad24)") (class "Default")
      (node (ref "LQ_KXXP144-SYSVG") (pin "24") (pinfunction "ADC0_DM3_24") (pintype "passive"))
    )
    (net (code "81") (name "unconnected-(LQ_KXXP144-SYSVG-ADC0_DP1-Pad17)") (class "Default")
      (node (ref "LQ_KXXP144-SYSVG") (pin "17") (pinfunction "ADC0_DP1_17") (pintype "passive"))
    )
    (net (code "82") (name "unconnected-(LQ_KXXP144-SYSVG-ADC0_DP3-Pad23)") (class "Default")
      (node (ref "LQ_KXXP144-SYSVG") (pin "23") (pinfunction "ADC0_DP3_23") (pintype "passive"))
    )
    (net (code "83") (name "unconnected-(LQ_KXXP144-SYSVG-ADC1-DP1-Pad19)") (class "Default")
      (node (ref "LQ_KXXP144-SYSVG") (pin "19") (pinfunction "ADC1-DP1_19") (pintype "passive"))
    )
    (net (code "84") (name "unconnected-(LQ_KXXP144-SYSVG-ADC1_DM3-Pad22)") (class "Default")
      (node (ref "LQ_KXXP144-SYSVG") (pin "22") (pinfunction "ADC1_DM3_22") (pintype "passive"))
    )
    (net (code "85") (name "unconnected-(LQ_KXXP144-SYSVG-ADC1_DP3-Pad21)") (class "Default")
      (node (ref "LQ_KXXP144-SYSVG") (pin "21") (pinfunction "ADC1_DP3_21") (pintype "passive"))
    )
    (net (code "86") (name "unconnected-(LQ_KXXP144-SYSVG-ADC1_SE18-Pad28)") (class "Default")
      (node (ref "LQ_KXXP144-SYSVG") (pin "28") (pinfunction "ADC1_SE18_28") (pintype "passive"))
    )
    (net (code "87") (name "unconnected-(LQ_KXXP144-SYSVG-BAT-Pad31)") (class "Default")
      (node (ref "LQ_KXXP144-SYSVG") (pin "31") (pinfunction "BAT_31") (pintype "passive"))
    )
    (net (code "88") (name "unconnected-(LQ_KXXP144-SYSVG-DAC0_OUT-Pad29)") (class "Default")
      (node (ref "LQ_KXXP144-SYSVG") (pin "29") (pinfunction "DAC0_OUT_29") (pintype "passive"))
    )
    (net (code "89") (name "unconnected-(LQ_KXXP144-SYSVG-DAC1_OUT-Pad30)") (class "Default")
      (node (ref "LQ_KXXP144-SYSVG") (pin "30") (pinfunction "DAC1_OUT_30") (pintype "passive"))
    )
    (net (code "90") (name "unconnected-(LQ_KXXP144-SYSVG-NC-Pad37)") (class "Default")
      (node (ref "LQ_KXXP144-SYSVG") (pin "37") (pinfunction "NC_37") (pintype "passive"))
    )
    (net (code "91") (name "unconnected-(LQ_KXXP144-SYSVG-NC-Pad39)") (class "Default")
      (node (ref "LQ_KXXP144-SYSVG") (pin "39") (pinfunction "NC_39") (pintype "passive"))
    )
    (net (code "92") (name "unconnected-(LQ_KXXP144-SYSVG-PTA0-Pad44)") (class "Default")
      (node (ref "LQ_KXXP144-SYSVG") (pin "44") (pinfunction "PTA0_44") (pintype "passive"))
    )
    (net (code "93") (name "unconnected-(LQ_KXXP144-SYSVG-PTA1-Pad40)") (class "Default")
      (node (ref "LQ_KXXP144-SYSVG") (pin "40") (pinfunction "PTA1_40") (pintype "passive"))
    )
    (net (code "94") (name "unconnected-(LQ_KXXP144-SYSVG-PTA2-Pad42)") (class "Default")
      (node (ref "LQ_KXXP144-SYSVG") (pin "42") (pinfunction "PTA2_42") (pintype "passive"))
    )
    (net (code "95") (name "unconnected-(LQ_KXXP144-SYSVG-PTA3-Pad46)") (class "Default")
      (node (ref "LQ_KXXP144-SYSVG") (pin "46") (pinfunction "PTA3_46") (pintype "passive"))
    )
    (net (code "96") (name "unconnected-(LQ_KXXP144-SYSVG-PTA4-Pad47)") (class "Default")
      (node (ref "LQ_KXXP144-SYSVG") (pin "47") (pinfunction "PTA4_47") (pintype "passive"))
    )
    (net (code "97") (name "unconnected-(LQ_KXXP144-SYSVG-PTA5-Pad48)") (class "Default")
      (node (ref "LQ_KXXP144-SYSVG") (pin "48") (pinfunction "PTA5_48") (pintype "passive"))
    )
    (net (code "98") (name "unconnected-(LQ_KXXP144-SYSVG-PTA6-Pad49)") (class "Default")
      (node (ref "LQ_KXXP144-SYSVG") (pin "49") (pinfunction "PTA6_49") (pintype "passive"))
    )
    (net (code "99") (name "unconnected-(LQ_KXXP144-SYSVG-PTA7-Pad50)") (class "Default")
      (node (ref "LQ_KXXP144-SYSVG") (pin "50") (pinfunction "PTA7_50") (pintype "passive"))
    )
    (net (code "100") (name "unconnected-(LQ_KXXP144-SYSVG-PTA9-Pad52)") (class "Default")
      (node (ref "LQ_KXXP144-SYSVG") (pin "52") (pinfunction "PTA9_52") (pintype "passive"))
    )
    (net (code "101") (name "unconnected-(LQ_KXXP144-SYSVG-PTA10-Pad53)") (class "Default")
      (node (ref "LQ_KXXP144-SYSVG") (pin "53") (pinfunction "PTA10_53") (pintype "passive"))
    )
    (net (code "102") (name "unconnected-(LQ_KXXP144-SYSVG-PTA11-Pad54)") (class "Default")
      (node (ref "LQ_KXXP144-SYSVG") (pin "54") (pinfunction "PTA11_54") (pintype "passive"))
    )
    (net (code "103") (name "unconnected-(LQ_KXXP144-SYSVG-PTA14-Pad57)") (class "Default")
      (node (ref "LQ_KXXP144-SYSVG") (pin "57") (pinfunction "PTA14_57") (pintype "passive"))
    )
    (net (code "104") (name "unconnected-(LQ_KXXP144-SYSVG-PTA15-Pad58)") (class "Default")
      (node (ref "LQ_KXXP144-SYSVG") (pin "58") (pinfunction "PTA15_58") (pintype "passive"))
    )
    (net (code "105") (name "unconnected-(LQ_KXXP144-SYSVG-PTA17-Pad60)") (class "Default")
      (node (ref "LQ_KXXP144-SYSVG") (pin "60") (pinfunction "PTA17_60") (pintype "passive"))
    )
    (net (code "106") (name "unconnected-(LQ_KXXP144-SYSVG-PTA18-Pad61)") (class "Default")
      (node (ref "LQ_KXXP144-SYSVG") (pin "61") (pinfunction "PTA18_61") (pintype "passive"))
    )
    (net (code "107") (name "unconnected-(LQ_KXXP144-SYSVG-PTA24-Pad64)") (class "Default")
      (node (ref "LQ_KXXP144-SYSVG") (pin "64") (pinfunction "PTA24_64") (pintype "passive"))
    )
    (net (code "108") (name "unconnected-(LQ_KXXP144-SYSVG-PTA25-Pad63)") (class "Default")
      (node (ref "LQ_KXXP144-SYSVG") (pin "63") (pinfunction "PTA25_63") (pintype "passive"))
    )
    (net (code "109") (name "unconnected-(LQ_KXXP144-SYSVG-PTA26-Pad66)") (class "Default")
      (node (ref "LQ_KXXP144-SYSVG") (pin "66") (pinfunction "PTA26_66") (pintype "passive"))
    )
    (net (code "110") (name "unconnected-(LQ_KXXP144-SYSVG-PTA27-Pad65)") (class "Default")
      (node (ref "LQ_KXXP144-SYSVG") (pin "65") (pinfunction "PTA27_65") (pintype "passive"))
    )
    (net (code "111") (name "unconnected-(LQ_KXXP144-SYSVG-PTA28-Pad68)") (class "Default")
      (node (ref "LQ_KXXP144-SYSVG") (pin "68") (pinfunction "PTA28_68") (pintype "passive"))
    )
    (net (code "112") (name "unconnected-(LQ_KXXP144-SYSVG-PTA29-Pad67)") (class "Default")
      (node (ref "LQ_KXXP144-SYSVG") (pin "67") (pinfunction "PTA29_67") (pintype "passive"))
    )
    (net (code "113") (name "unconnected-(LQ_KXXP144-SYSVG-PTB4-Pad74)") (class "Default")
      (node (ref "LQ_KXXP144-SYSVG") (pin "74") (pinfunction "PTB4_74") (pintype "passive"))
    )
    (net (code "114") (name "unconnected-(LQ_KXXP144-SYSVG-PTB5-Pad73)") (class "Default")
      (node (ref "LQ_KXXP144-SYSVG") (pin "73") (pinfunction "PTB5_73") (pintype "passive"))
    )
    (net (code "115") (name "unconnected-(LQ_KXXP144-SYSVG-PTB6-Pad76)") (class "Default")
      (node (ref "LQ_KXXP144-SYSVG") (pin "76") (pinfunction "PTB6_76") (pintype "passive"))
    )
    (net (code "116") (name "unconnected-(LQ_KXXP144-SYSVG-PTB7-Pad75)") (class "Default")
      (node (ref "LQ_KXXP144-SYSVG") (pin "75") (pinfunction "PTB7_75") (pintype "passive"))
    )
    (net (code "117") (name "unconnected-(LQ_KXXP144-SYSVG-PTB8-Pad78)") (class "Default")
      (node (ref "LQ_KXXP144-SYSVG") (pin "78") (pinfunction "PTB8_78") (pintype "passive"))
    )
    (net (code "118") (name "unconnected-(LQ_KXXP144-SYSVG-PTB9-Pad77)") (class "Default")
      (node (ref "LQ_KXXP144-SYSVG") (pin "77") (pinfunction "PTB9_77") (pintype "passive"))
    )
    (net (code "119") (name "unconnected-(LQ_KXXP144-SYSVG-PTB18-Pad84)") (class "Default")
      (node (ref "LQ_KXXP144-SYSVG") (pin "84") (pinfunction "PTB18_84") (pintype "passive"))
    )
    (net (code "120") (name "unconnected-(LQ_KXXP144-SYSVG-PTB23-Pad87)") (class "Default")
      (node (ref "LQ_KXXP144-SYSVG") (pin "87") (pinfunction "PTB23_87") (pintype "passive"))
    )
    (net (code "121") (name "unconnected-(LQ_KXXP144-SYSVG-PTC0-Pad90)") (class "Default")
      (node (ref "LQ_KXXP144-SYSVG") (pin "90") (pinfunction "PTC0_90") (pintype "passive"))
    )
    (net (code "122") (name "unconnected-(LQ_KXXP144-SYSVG-PTC5-Pad93)") (class "Default")
      (node (ref "LQ_KXXP144-SYSVG") (pin "93") (pinfunction "PTC5_93") (pintype "passive"))
    )
    (net (code "123") (name "unconnected-(LQ_KXXP144-SYSVG-PTC12-Pad102)") (class "Default")
      (node (ref "LQ_KXXP144-SYSVG") (pin "102") (pinfunction "PTC12_102") (pintype "passive"))
    )
    (net (code "124") (name "unconnected-(LQ_KXXP144-SYSVG-PTC17-Pad105)") (class "Default")
      (node (ref "LQ_KXXP144-SYSVG") (pin "105") (pinfunction "PTC17_105") (pintype "passive"))
    )
    (net (code "125") (name "unconnected-(LQ_KXXP144-SYSVG-PTD8-Pad118)") (class "Default")
      (node (ref "LQ_KXXP144-SYSVG") (pin "118") (pinfunction "PTD8_118") (pintype "passive"))
    )
    (net (code "126") (name "unconnected-(LQ_KXXP144-SYSVG-PTD9-Pad117)") (class "Default")
      (node (ref "LQ_KXXP144-SYSVG") (pin "117") (pinfunction "PTD9_117") (pintype "passive"))
    )
    (net (code "127") (name "unconnected-(LQ_KXXP144-SYSVG-PTD10-Pad120)") (class "Default")
      (node (ref "LQ_KXXP144-SYSVG") (pin "120") (pinfunction "PTD10_120") (pintype "passive"))
    )
    (net (code "128") (name "unconnected-(LQ_KXXP144-SYSVG-PTD11-Pad119)") (class "Default")
      (node (ref "LQ_KXXP144-SYSVG") (pin "119") (pinfunction "PTD11_119") (pintype "passive"))
    )
    (net (code "129") (name "unconnected-(LQ_KXXP144-SYSVG-PTD12-Pad122)") (class "Default")
      (node (ref "LQ_KXXP144-SYSVG") (pin "122") (pinfunction "PTD12_122") (pintype "passive"))
    )
    (net (code "130") (name "unconnected-(LQ_KXXP144-SYSVG-PTD13-Pad121)") (class "Default")
      (node (ref "LQ_KXXP144-SYSVG") (pin "121") (pinfunction "PTD13_121") (pintype "passive"))
    )
    (net (code "131") (name "unconnected-(LQ_KXXP144-SYSVG-PTD14-Pad124)") (class "Default")
      (node (ref "LQ_KXXP144-SYSVG") (pin "124") (pinfunction "PTD14_124") (pintype "passive"))
    )
    (net (code "132") (name "unconnected-(LQ_KXXP144-SYSVG-PTD15-Pad123)") (class "Default")
      (node (ref "LQ_KXXP144-SYSVG") (pin "123") (pinfunction "PTD15_123") (pintype "passive"))
    )
    (net (code "133") (name "unconnected-(LQ_KXXP144-SYSVG-PTE6-Pad7)") (class "Default")
      (node (ref "LQ_KXXP144-SYSVG") (pin "7") (pinfunction "PTE6_7") (pintype "passive"))
    )
    (net (code "134") (name "unconnected-(LQ_KXXP144-SYSVG-PTE26-Pad34)") (class "Default")
      (node (ref "LQ_KXXP144-SYSVG") (pin "34") (pinfunction "PTE26_34") (pintype "passive"))
    )
    (net (code "135") (name "unconnected-(LQ_KXXP144-SYSVG-PTE27-Pad35)") (class "Default")
      (node (ref "LQ_KXXP144-SYSVG") (pin "35") (pinfunction "PTE27_35") (pintype "passive"))
    )
    (net (code "136") (name "unconnected-(LQ_KXXP144-SYSVG-PTE28-Pad36)") (class "Default")
      (node (ref "LQ_KXXP144-SYSVG") (pin "36") (pinfunction "PTE28_36") (pintype "passive"))
    )
    (net (code "137") (name "unconnected-(LQ_KXXP144-SYSVG-RESET-Pad38)") (class "Default")
      (node (ref "LQ_KXXP144-SYSVG") (pin "38") (pinfunction "RESET_38") (pintype "passive"))
    )
    (net (code "138") (name "unconnected-(LQ_KXXP144-SYSVG-USB0_DM-Pad15)") (class "Default")
      (node (ref "LQ_KXXP144-SYSVG") (pin "15") (pinfunction "USB0_DM_15") (pintype "passive"))
    )
    (net (code "139") (name "unconnected-(LQ_KXXP144-SYSVG-USB0_DP-Pad14)") (class "Default")
      (node (ref "LQ_KXXP144-SYSVG") (pin "14") (pinfunction "USB0_DP_14") (pintype "passive"))
    )
    (net (code "140") (name "unconnected-(LQ_KXXP144-SYSVG-VREFH-Pad25)") (class "Default")
      (node (ref "LQ_KXXP144-SYSVG") (pin "25") (pinfunction "VREFH_25") (pintype "passive"))
    )
    (net (code "141") (name "unconnected-(LQ_KXXP144-SYSVG-VREGIN-Pad16)") (class "Default")
      (node (ref "LQ_KXXP144-SYSVG") (pin "16") (pinfunction "VREGIN_16") (pintype "passive"))
    )
    (net (code "142") (name "unconnected-(OLED-Pad7)") (class "Default")
      (node (ref "OLED") (pin "7") (pinfunction "7_7") (pintype "passive+no_connect"))
    )
    (net (code "143") (name "unconnected-(RP1-Pad3)") (class "Default")
      (node (ref "RP1") (pin "3") (pintype "passive"))
    )
    (net (code "144") (name "unconnected-(RP1-Pad4)") (class "Default")
      (node (ref "RP1") (pin "4") (pintype "passive"))
    )
    (net (code "145") (name "unconnected-(RP2-Pad5)") (class "Default")
      (node (ref "RP2") (pin "5") (pintype "passive"))
    )
    (net (code "146") (name "unconnected-(SW-Pad3)") (class "Default")
      (node (ref "SW") (pin "3") (pinfunction "3_3") (pintype "passive+no_connect"))
    )
    (net (code "147") (name "unconnected-(VR-A-Pad1)") (class "Default")
      (node (ref "VR") (pin "1") (pinfunction "A_1") (pintype "passive"))
    )
  )
)
